# CONTROL_PROJECT.net
KiCad netlist of a schematic drawn in EAGLE
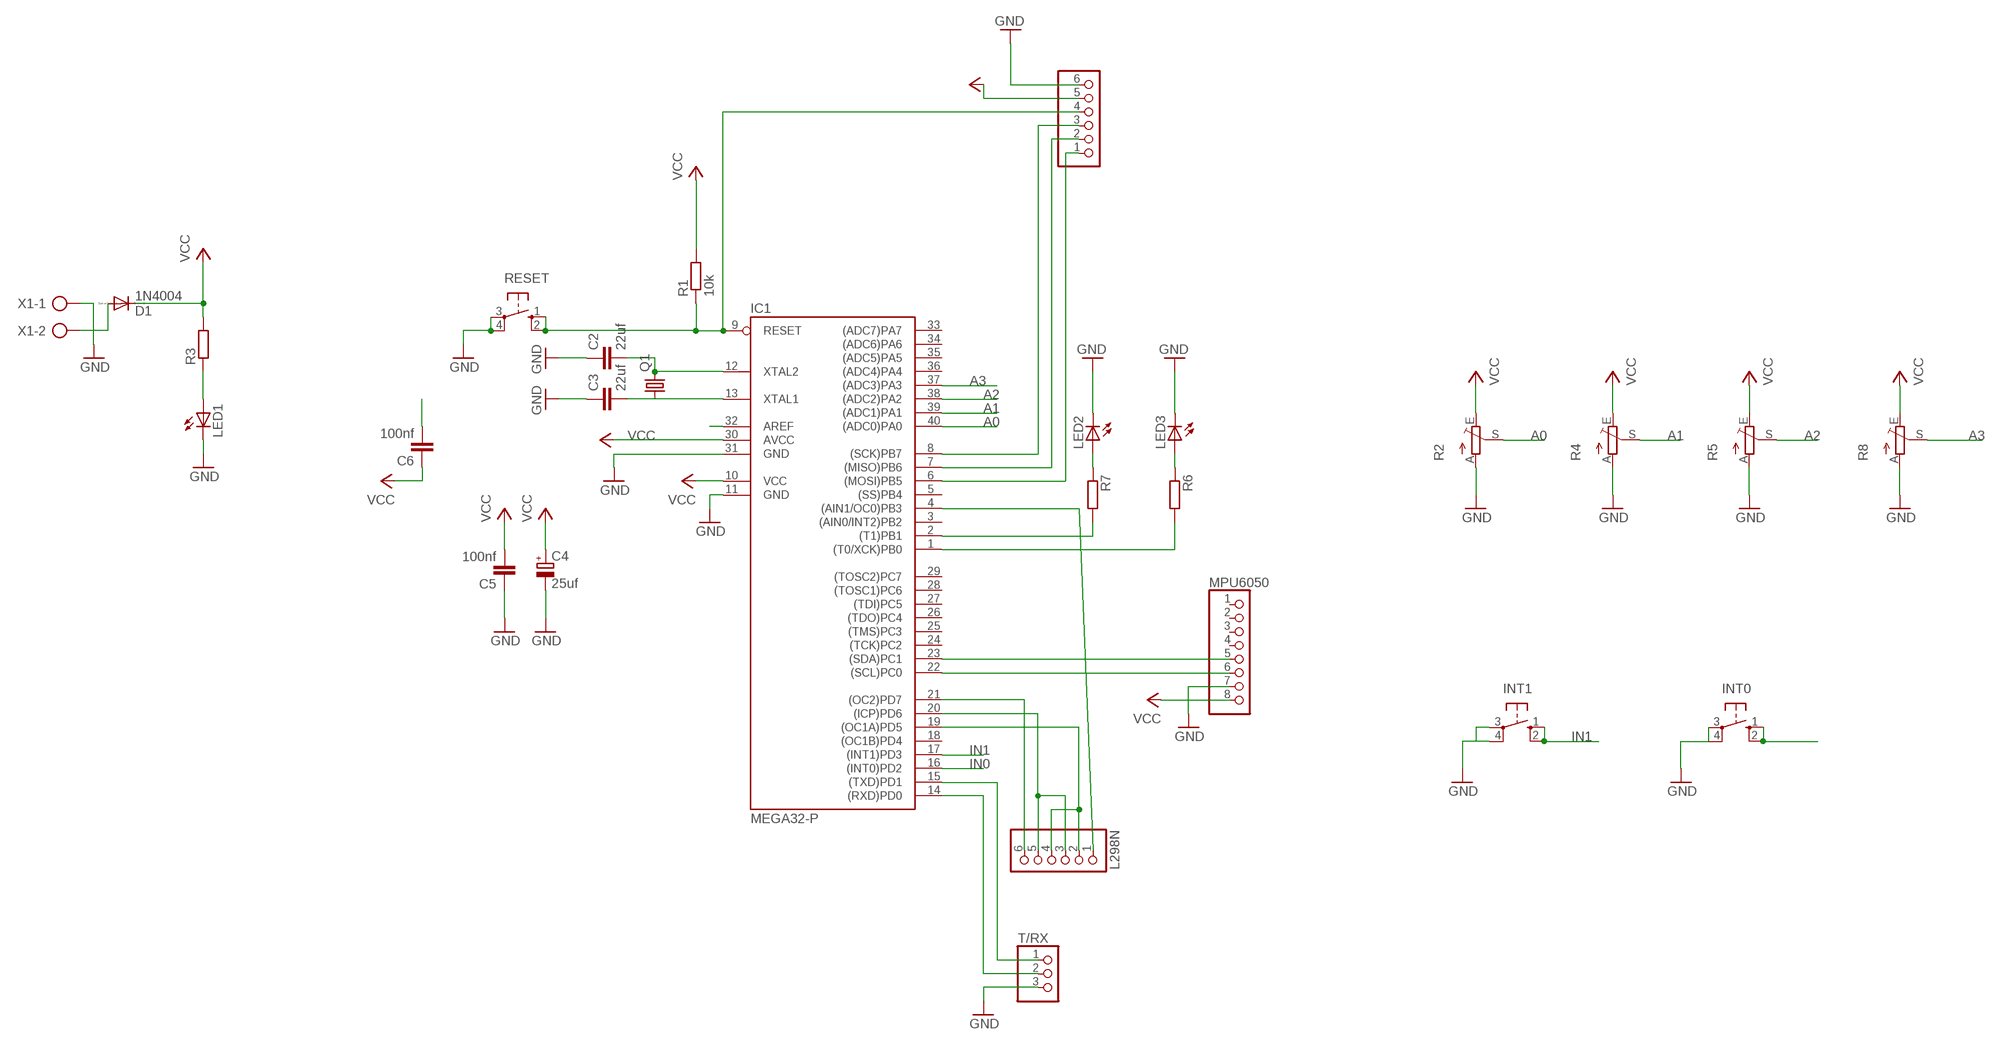
[diagram p0: schematic, sheet 1]

(export (version "E")
  (design (tool "Eeschema 10.0.6"))
  (components
    (comp (ref "C2")
      (value "22uf")
      (footprint "eagle-import:C050-025X075")
      (libsource (lib "eagle-import") (part "C-EU050-025X075"))
    )
    (comp (ref "C3")
      (value "22uf")
      (footprint "eagle-import:C050-025X075")
      (libsource (lib "eagle-import") (part "C-EU050-025X075"))
    )
    (comp (ref "C4")
      (value "25uf")
      (footprint "eagle-import:E1,8-4")
      (libsource (lib "eagle-import") (part "CPOL-EUE1.8-4"))
    )
    (comp (ref "C5")
      (value "100nf")
      (footprint "eagle-import:C050-025X075")
      (libsource (lib "eagle-import") (part "C-EU050-025X075"))
    )
    (comp (ref "C6")
      (value "100nf")
      (footprint "eagle-import:C050-025X075")
      (libsource (lib "eagle-import") (part "C-EU050-025X075"))
    )
    (comp (ref "D1")
      (value "1N4004")
      (footprint "eagle-import:DO41-10")
      (libsource (lib "eagle-import") (part "1N4004"))
    )
    (comp (ref "IC1")
      (value "MEGA32-P")
      (footprint "eagle-import:DIL40")
      (fields (field (name "MPN") "ATMEGA32-16PU"))
      (libsource (lib "eagle-import") (part "MEGA32-P"))
    )
    (comp (ref "INT0")
      (value "10-XX")
      (footprint "eagle-import:B3F-10XX")
      (fields (field (name "MPN") "B3F-1000"))
      (libsource (lib "eagle-import") (part "10-XX"))
    )
    (comp (ref "INT1")
      (value "10-XX")
      (footprint "eagle-import:B3F-10XX")
      (fields (field (name "MPN") "B3F-1000"))
      (libsource (lib "eagle-import") (part "10-XX"))
    )
    (comp (ref "L298N")
      (value "PINHD-1X6")
      (footprint "eagle-import:1X06")
      (libsource (lib "eagle-import") (part "PINHD-1X6"))
    )
    (comp (ref "LED1")
      (value "LED5MM")
      (footprint "eagle-import:LED5MM")
      (libsource (lib "eagle-import") (part "LED5MM"))
    )
    (comp (ref "LED2")
      (value "LED5MM")
      (footprint "eagle-import:LED5MM")
      (libsource (lib "eagle-import") (part "LED5MM"))
    )
    (comp (ref "LED3")
      (value "LED5MM")
      (footprint "eagle-import:LED5MM")
      (libsource (lib "eagle-import") (part "LED5MM"))
    )
    (comp (ref "MPU6050")
      (value "PINHD-1X8")
      (footprint "eagle-import:1X08")
      (libsource (lib "eagle-import") (part "PINHD-1X8"))
    )
    (comp (ref "PROG")
      (value "PINHD-1X6")
      (footprint "eagle-import:1X06")
      (libsource (lib "eagle-import") (part "PINHD-1X6"))
    )
    (comp (ref "Q1")
      (value "CRYSTALHC49U-V")
      (footprint "eagle-import:HC49U-V")
      (libsource (lib "eagle-import") (part "CRYSTALHC49U-V"))
    )
    (comp (ref "R1")
      (value "10k")
      (footprint "eagle-import:0207_7")
      (libsource (lib "eagle-import") (part "R-EU_0207/7"))
    )
    (comp (ref "R2")
      (value "TRIM_EU-RJ6")
      (footprint "eagle-import:RJ6")
      (libsource (lib "eagle-import") (part "TRIM_EU-RJ6"))
    )
    (comp (ref "R3")
      (value "R-EU_0207/7")
      (footprint "eagle-import:0207_7")
      (libsource (lib "eagle-import") (part "R-EU_0207/7"))
    )
    (comp (ref "R4")
      (value "TRIM_EU-RJ6")
      (footprint "eagle-import:RJ6")
      (libsource (lib "eagle-import") (part "TRIM_EU-RJ6"))
    )
    (comp (ref "R5")
      (value "TRIM_EU-RJ6")
      (footprint "eagle-import:RJ6")
      (libsource (lib "eagle-import") (part "TRIM_EU-RJ6"))
    )
    (comp (ref "R6")
      (value "R-EU_0207/7")
      (footprint "eagle-import:0207_7")
      (libsource (lib "eagle-import") (part "R-EU_0207/7"))
    )
    (comp (ref "R7")
      (value "R-EU_0207/7")
      (footprint "eagle-import:0207_7")
      (libsource (lib "eagle-import") (part "R-EU_0207/7"))
    )
    (comp (ref "R8")
      (value "TRIM_EU-RJ6")
      (footprint "eagle-import:RJ6")
      (libsource (lib "eagle-import") (part "TRIM_EU-RJ6"))
    )
    (comp (ref "RESET")
      (value "10-XX")
      (footprint "eagle-import:B3F-10XX")
      (fields (field (name "MPN") "B3F-1000"))
      (libsource (lib "eagle-import") (part "10-XX"))
    )
    (comp (ref "T/RX")
      (value "PINHD-1X3")
      (footprint "eagle-import:1X03")
      (libsource (lib "eagle-import") (part "PINHD-1X3"))
    )
    (comp (ref "X1")
      (value "AK300/2")
      (footprint "eagle-import:AK300_2")
      (libsource (lib "eagle-import") (part "AK300/2"))
    )
  )
  (nets
    (net (code "1") (name "/A0") (class "Default")
      (node (ref "IC1") (pin "40") (pinfunction "(ADC0)PA0_40") (pintype "bidirectional"))
      (node (ref "R2") (pin "S") (pinfunction "S_S") (pintype "passive"))
    )
    (net (code "2") (name "/A1") (class "Default")
      (node (ref "IC1") (pin "39") (pinfunction "(ADC1)PA1_39") (pintype "bidirectional"))
      (node (ref "R4") (pin "S") (pinfunction "S_S") (pintype "passive"))
    )
    (net (code "3") (name "/A2") (class "Default")
      (node (ref "IC1") (pin "38") (pinfunction "(ADC2)PA2_38") (pintype "bidirectional"))
      (node (ref "R5") (pin "S") (pinfunction "S_S") (pintype "passive"))
    )
    (net (code "4") (name "/A3") (class "Default")
      (node (ref "IC1") (pin "37") (pinfunction "(ADC3)PA3_37") (pintype "bidirectional"))
      (node (ref "R8") (pin "S") (pinfunction "S_S") (pintype "passive"))
    )
    (net (code "5") (name "/AREF") (class "Default")
      (node (ref "C6") (pin "2") (pinfunction "2_2") (pintype "passive"))
      (node (ref "IC1") (pin "32") (pinfunction "AREF_32") (pintype "passive"))
    )
    (net (code "6") (name "/IN0") (class "Default")
      (node (ref "IC1") (pin "16") (pinfunction "(INT0)PD2_16") (pintype "bidirectional"))
      (node (ref "INT0") (pin "1") (pinfunction "S_1") (pintype "passive"))
      (node (ref "INT0") (pin "2") (pinfunction "S1_2") (pintype "passive"))
    )
    (net (code "7") (name "/IN1") (class "Default")
      (node (ref "IC1") (pin "17") (pinfunction "(INT1)PD3_17") (pintype "bidirectional"))
      (node (ref "INT1") (pin "1") (pinfunction "S_1") (pintype "passive"))
      (node (ref "INT1") (pin "2") (pinfunction "S1_2") (pintype "passive"))
    )
    (net (code "8") (name "GND") (class "Default")
      (node (ref "C2") (pin "1") (pinfunction "1_1") (pintype "passive"))
      (node (ref "C3") (pin "1") (pinfunction "1_1") (pintype "passive"))
      (node (ref "C4") (pin "-") (pinfunction "-_-") (pintype "passive"))
      (node (ref "C5") (pin "1") (pinfunction "1_1") (pintype "passive"))
      (node (ref "IC1") (pin "11") (pinfunction "GND_11") (pintype "power_in"))
      (node (ref "IC1") (pin "31") (pinfunction "GND_31") (pintype "power_in"))
      (node (ref "INT0") (pin "3") (pinfunction "P_3") (pintype "passive"))
      (node (ref "INT0") (pin "4") (pinfunction "P1_4") (pintype "passive"))
      (node (ref "INT1") (pin "3") (pinfunction "P_3") (pintype "passive"))
      (node (ref "INT1") (pin "4") (pinfunction "P1_4") (pintype "passive"))
      (node (ref "LED1") (pin "K") (pinfunction "C_K") (pintype "passive"))
      (node (ref "LED2") (pin "K") (pinfunction "C_K") (pintype "passive"))
      (node (ref "LED3") (pin "K") (pinfunction "C_K") (pintype "passive"))
      (node (ref "MPU6050") (pin "7") (pinfunction "7_7") (pintype "passive"))
      (node (ref "PROG") (pin "6") (pinfunction "6_6") (pintype "passive"))
      (node (ref "R2") (pin "A") (pinfunction "A_A") (pintype "passive"))
      (node (ref "R4") (pin "A") (pinfunction "A_A") (pintype "passive"))
      (node (ref "R5") (pin "A") (pinfunction "A_A") (pintype "passive"))
      (node (ref "R8") (pin "A") (pinfunction "A_A") (pintype "passive"))
      (node (ref "RESET") (pin "3") (pinfunction "P_3") (pintype "passive"))
      (node (ref "RESET") (pin "4") (pinfunction "P1_4") (pintype "passive"))
      (node (ref "T/RX") (pin "3") (pinfunction "3_3") (pintype "passive"))
      (node (ref "X1") (pin "1") (pinfunction "KL_1") (pintype "passive"))
    )
    (net (code "9") (name "Net-(IC1-(AIN1{slash}OC0)PB3)") (class "Default")
      (node (ref "IC1") (pin "4") (pinfunction "(AIN1/OC0)PB3_4") (pintype "bidirectional"))
      (node (ref "L298N") (pin "1") (pinfunction "1_1") (pintype "passive"))
    )
    (net (code "10") (name "Net-(IC1-(ICP)PD6)") (class "Default")
      (node (ref "IC1") (pin "20") (pinfunction "(ICP)PD6_20") (pintype "bidirectional"))
      (node (ref "L298N") (pin "3") (pinfunction "3_3") (pintype "passive"))
      (node (ref "L298N") (pin "5") (pinfunction "5_5") (pintype "passive"))
    )
    (net (code "11") (name "Net-(IC1-(MISO)PB6)") (class "Default")
      (node (ref "IC1") (pin "7") (pinfunction "(MISO)PB6_7") (pintype "bidirectional"))
      (node (ref "PROG") (pin "2") (pinfunction "2_2") (pintype "passive"))
    )
    (net (code "12") (name "Net-(IC1-(MOSI)PB5)") (class "Default")
      (node (ref "IC1") (pin "6") (pinfunction "(MOSI)PB5_6") (pintype "bidirectional"))
      (node (ref "PROG") (pin "1") (pinfunction "1_1") (pintype "passive"))
    )
    (net (code "13") (name "Net-(IC1-(OC1A)PD5)") (class "Default")
      (node (ref "IC1") (pin "19") (pinfunction "(OC1A)PD5_19") (pintype "bidirectional"))
      (node (ref "L298N") (pin "2") (pinfunction "2_2") (pintype "passive"))
      (node (ref "L298N") (pin "4") (pinfunction "4_4") (pintype "passive"))
    )
    (net (code "14") (name "Net-(IC1-(OC2)PD7)") (class "Default")
      (node (ref "IC1") (pin "21") (pinfunction "(OC2)PD7_21") (pintype "bidirectional"))
      (node (ref "L298N") (pin "6") (pinfunction "6_6") (pintype "passive"))
    )
    (net (code "15") (name "Net-(IC1-(RXD)PD0)") (class "Default")
      (node (ref "IC1") (pin "14") (pinfunction "(RXD)PD0_14") (pintype "bidirectional"))
      (node (ref "T/RX") (pin "2") (pinfunction "2_2") (pintype "passive"))
    )
    (net (code "16") (name "Net-(IC1-(SCK)PB7)") (class "Default")
      (node (ref "IC1") (pin "8") (pinfunction "(SCK)PB7_8") (pintype "bidirectional"))
      (node (ref "PROG") (pin "3") (pinfunction "3_3") (pintype "passive"))
    )
    (net (code "17") (name "Net-(IC1-(SCL)PC0)") (class "Default")
      (node (ref "IC1") (pin "22") (pinfunction "(SCL)PC0_22") (pintype "bidirectional"))
      (node (ref "MPU6050") (pin "6") (pinfunction "6_6") (pintype "passive"))
    )
    (net (code "18") (name "Net-(IC1-(SDA)PC1)") (class "Default")
      (node (ref "IC1") (pin "23") (pinfunction "(SDA)PC1_23") (pintype "bidirectional"))
      (node (ref "MPU6050") (pin "5") (pinfunction "5_5") (pintype "passive"))
    )
    (net (code "19") (name "Net-(IC1-(T0{slash}XCK)PB0)") (class "Default")
      (node (ref "IC1") (pin "1") (pinfunction "(T0/XCK)PB0_1") (pintype "bidirectional"))
      (node (ref "R6") (pin "2") (pinfunction "2_2") (pintype "passive"))
    )
    (net (code "20") (name "Net-(IC1-(T1)PB1)") (class "Default")
      (node (ref "IC1") (pin "2") (pinfunction "(T1)PB1_2") (pintype "bidirectional"))
      (node (ref "R7") (pin "2") (pinfunction "2_2") (pintype "passive"))
    )
    (net (code "21") (name "Net-(IC1-(TXD)PD1)") (class "Default")
      (node (ref "IC1") (pin "15") (pinfunction "(TXD)PD1_15") (pintype "bidirectional"))
      (node (ref "T/RX") (pin "1") (pinfunction "1_1") (pintype "passive"))
    )
    (net (code "22") (name "Net-(IC1-RESET)") (class "Default")
      (node (ref "IC1") (pin "9") (pinfunction "RESET_9") (pintype "input"))
      (node (ref "PROG") (pin "4") (pinfunction "4_4") (pintype "passive"))
      (node (ref "R1") (pin "1") (pinfunction "1_1") (pintype "passive"))
      (node (ref "RESET") (pin "1") (pinfunction "S_1") (pintype "passive"))
      (node (ref "RESET") (pin "2") (pinfunction "S1_2") (pintype "passive"))
    )
    (net (code "23") (name "Net-(IC1-XTAL1)") (class "Default")
      (node (ref "C3") (pin "2") (pinfunction "2_2") (pintype "passive"))
      (node (ref "IC1") (pin "13") (pinfunction "XTAL1_13") (pintype "bidirectional"))
      (node (ref "Q1") (pin "1") (pinfunction "1_1") (pintype "passive"))
    )
    (net (code "24") (name "Net-(IC1-XTAL2)") (class "Default")
      (node (ref "C2") (pin "2") (pinfunction "2_2") (pintype "passive"))
      (node (ref "IC1") (pin "12") (pinfunction "XTAL2_12") (pintype "bidirectional"))
      (node (ref "Q1") (pin "2") (pinfunction "2_2") (pintype "passive"))
    )
    (net (code "25") (name "Net-(LED1-PadA)") (class "Default")
      (node (ref "LED1") (pin "A") (pinfunction "A_A") (pintype "passive"))
      (node (ref "R3") (pin "1") (pinfunction "1_1") (pintype "passive"))
    )
    (net (code "26") (name "Net-(LED2-PadA)") (class "Default")
      (node (ref "LED2") (pin "A") (pinfunction "A_A") (pintype "passive"))
      (node (ref "R7") (pin "1") (pinfunction "1_1") (pintype "passive"))
    )
    (net (code "27") (name "Net-(LED3-PadA)") (class "Default")
      (node (ref "LED3") (pin "A") (pinfunction "A_A") (pintype "passive"))
      (node (ref "R6") (pin "1") (pinfunction "1_1") (pintype "passive"))
    )
    (net (code "28") (name "Net-(X1B-KL)") (class "Default")
      (node (ref "D1") (pin "A") (pinfunction "A_A") (pintype "passive"))
      (node (ref "X1") (pin "2") (pinfunction "KL_2") (pintype "passive"))
    )
    (net (code "29") (name "VCC") (class "Default")
      (node (ref "C4") (pin "+") (pinfunction "+_+") (pintype "passive"))
      (node (ref "C5") (pin "2") (pinfunction "2_2") (pintype "passive"))
      (node (ref "C6") (pin "1") (pinfunction "1_1") (pintype "passive"))
      (node (ref "D1") (pin "C") (pinfunction "C_C") (pintype "passive"))
      (node (ref "IC1") (pin "10") (pinfunction "VCC_10") (pintype "power_in"))
      (node (ref "IC1") (pin "30") (pinfunction "AVCC_30") (pintype "power_in"))
      (node (ref "MPU6050") (pin "8") (pinfunction "8_8") (pintype "passive"))
      (node (ref "PROG") (pin "5") (pinfunction "5_5") (pintype "passive"))
      (node (ref "R1") (pin "2") (pinfunction "2_2") (pintype "passive"))
      (node (ref "R2") (pin "E") (pinfunction "E_E") (pintype "passive"))
      (node (ref "R3") (pin "2") (pinfunction "2_2") (pintype "passive"))
      (node (ref "R4") (pin "E") (pinfunction "E_E") (pintype "passive"))
      (node (ref "R5") (pin "E") (pinfunction "E_E") (pintype "passive"))
      (node (ref "R8") (pin "E") (pinfunction "E_E") (pintype "passive"))
    )
    (net (code "30") (name "unconnected-(IC1-(ADC4)PA4-Pad36)") (class "Default")
      (node (ref "IC1") (pin "36") (pinfunction "(ADC4)PA4_36") (pintype "bidirectional"))
    )
    (net (code "31") (name "unconnected-(IC1-(ADC5)PA5-Pad35)") (class "Default")
      (node (ref "IC1") (pin "35") (pinfunction "(ADC5)PA5_35") (pintype "bidirectional"))
    )
    (net (code "32") (name "unconnected-(IC1-(ADC6)PA6-Pad34)") (class "Default")
      (node (ref "IC1") (pin "34") (pinfunction "(ADC6)PA6_34") (pintype "bidirectional"))
    )
    (net (code "33") (name "unconnected-(IC1-(ADC7)PA7-Pad33)") (class "Default")
      (node (ref "IC1") (pin "33") (pinfunction "(ADC7)PA7_33") (pintype "bidirectional"))
    )
    (net (code "34") (name "unconnected-(IC1-(AIN0{slash}INT2)PB2-Pad3)") (class "Default")
      (node (ref "IC1") (pin "3") (pinfunction "(AIN0/INT2)PB2_3") (pintype "bidirectional"))
    )
    (net (code "35") (name "unconnected-(IC1-(OC1B)PD4-Pad18)") (class "Default")
      (node (ref "IC1") (pin "18") (pinfunction "(OC1B)PD4_18") (pintype "bidirectional"))
    )
    (net (code "36") (name "unconnected-(IC1-(SS)PB4-Pad5)") (class "Default")
      (node (ref "IC1") (pin "5") (pinfunction "(SS)PB4_5") (pintype "bidirectional"))
    )
    (net (code "37") (name "unconnected-(IC1-(TCK)PC2-Pad24)") (class "Default")
      (node (ref "IC1") (pin "24") (pinfunction "(TCK)PC2_24") (pintype "bidirectional"))
    )
    (net (code "38") (name "unconnected-(IC1-(TDI)PC5-Pad27)") (class "Default")
      (node (ref "IC1") (pin "27") (pinfunction "(TDI)PC5_27") (pintype "bidirectional"))
    )
    (net (code "39") (name "unconnected-(IC1-(TDO)PC4-Pad26)") (class "Default")
      (node (ref "IC1") (pin "26") (pinfunction "(TDO)PC4_26") (pintype "bidirectional"))
    )
    (net (code "40") (name "unconnected-(IC1-(TMS)PC3-Pad25)") (class "Default")
      (node (ref "IC1") (pin "25") (pinfunction "(TMS)PC3_25") (pintype "bidirectional"))
    )
    (net (code "41") (name "unconnected-(IC1-(TOSC1)PC6-Pad28)") (class "Default")
      (node (ref "IC1") (pin "28") (pinfunction "(TOSC1)PC6_28") (pintype "bidirectional"))
    )
    (net (code "42") (name "unconnected-(IC1-(TOSC2)PC7-Pad29)") (class "Default")
      (node (ref "IC1") (pin "29") (pinfunction "(TOSC2)PC7_29") (pintype "bidirectional"))
    )
    (net (code "43") (name "unconnected-(MPU6050-Pad1)") (class "Default")
      (node (ref "MPU6050") (pin "1") (pinfunction "1_1") (pintype "passive"))
    )
    (net (code "44") (name "unconnected-(MPU6050-Pad2)") (class "Default")
      (node (ref "MPU6050") (pin "2") (pinfunction "2_2") (pintype "passive"))
    )
    (net (code "45") (name "unconnected-(MPU6050-Pad3)") (class "Default")
      (node (ref "MPU6050") (pin "3") (pinfunction "3_3") (pintype "passive"))
    )
    (net (code "46") (name "unconnected-(MPU6050-Pad4)") (class "Default")
      (node (ref "MPU6050") (pin "4") (pinfunction "4_4") (pintype "passive"))
    )
  )
)
